# DotStix.net
KiCad netlist of a schematic drawn in EAGLE
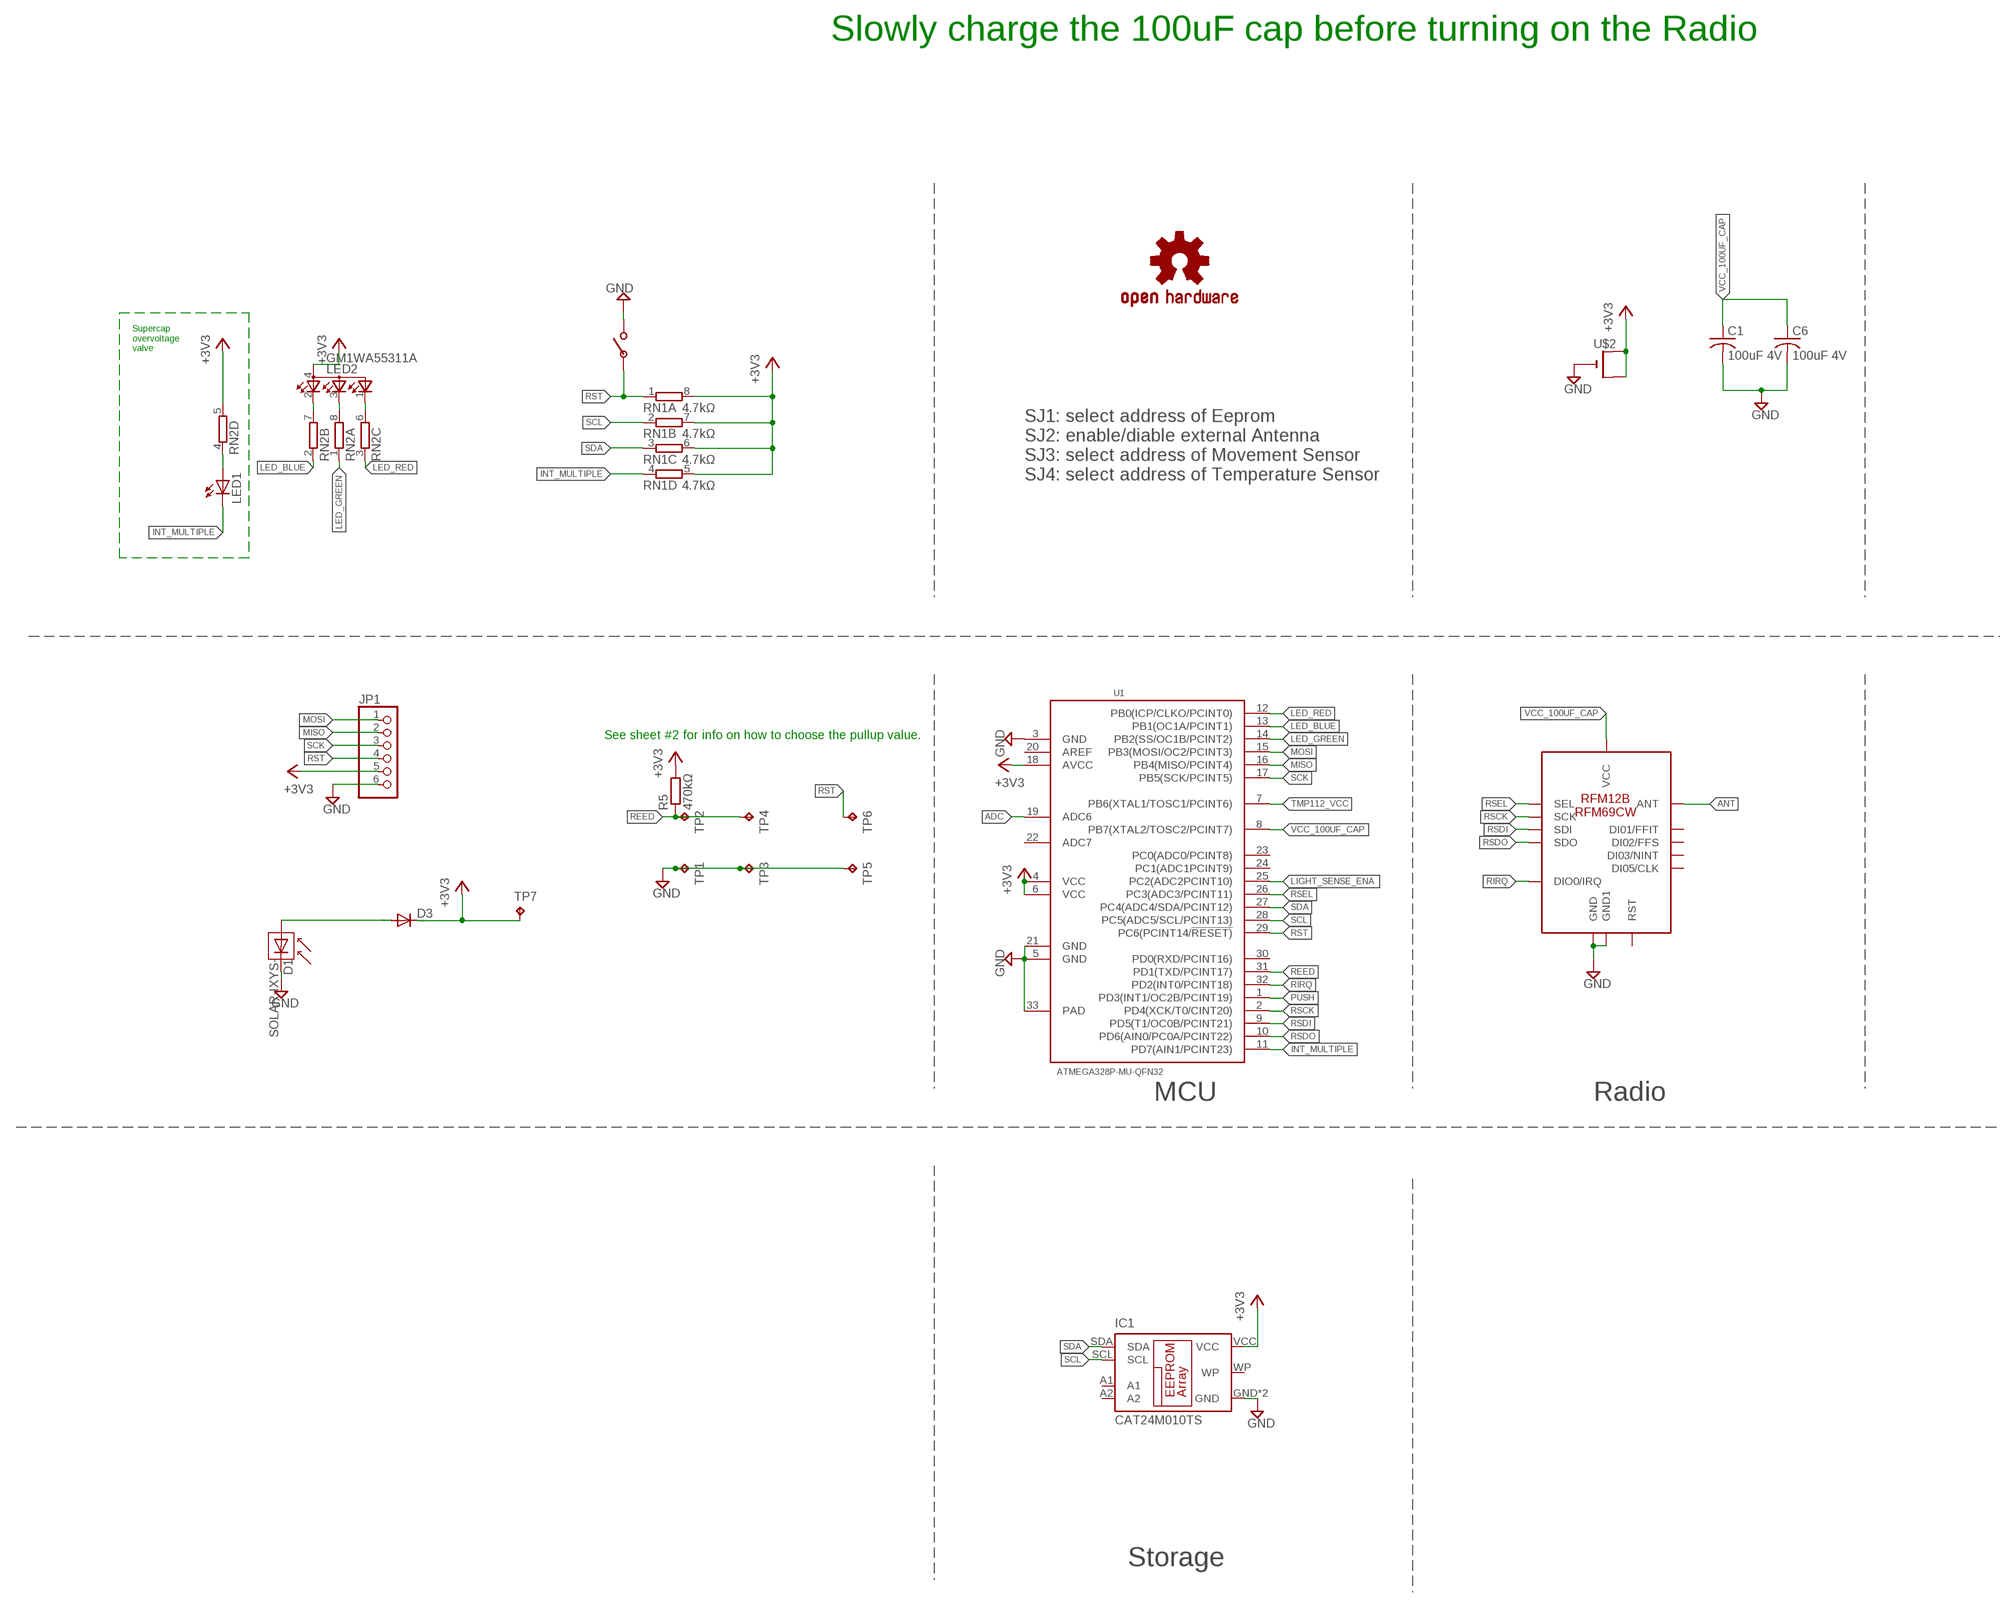
[diagram p0: schematic, sheet 1, part 1 of 2]
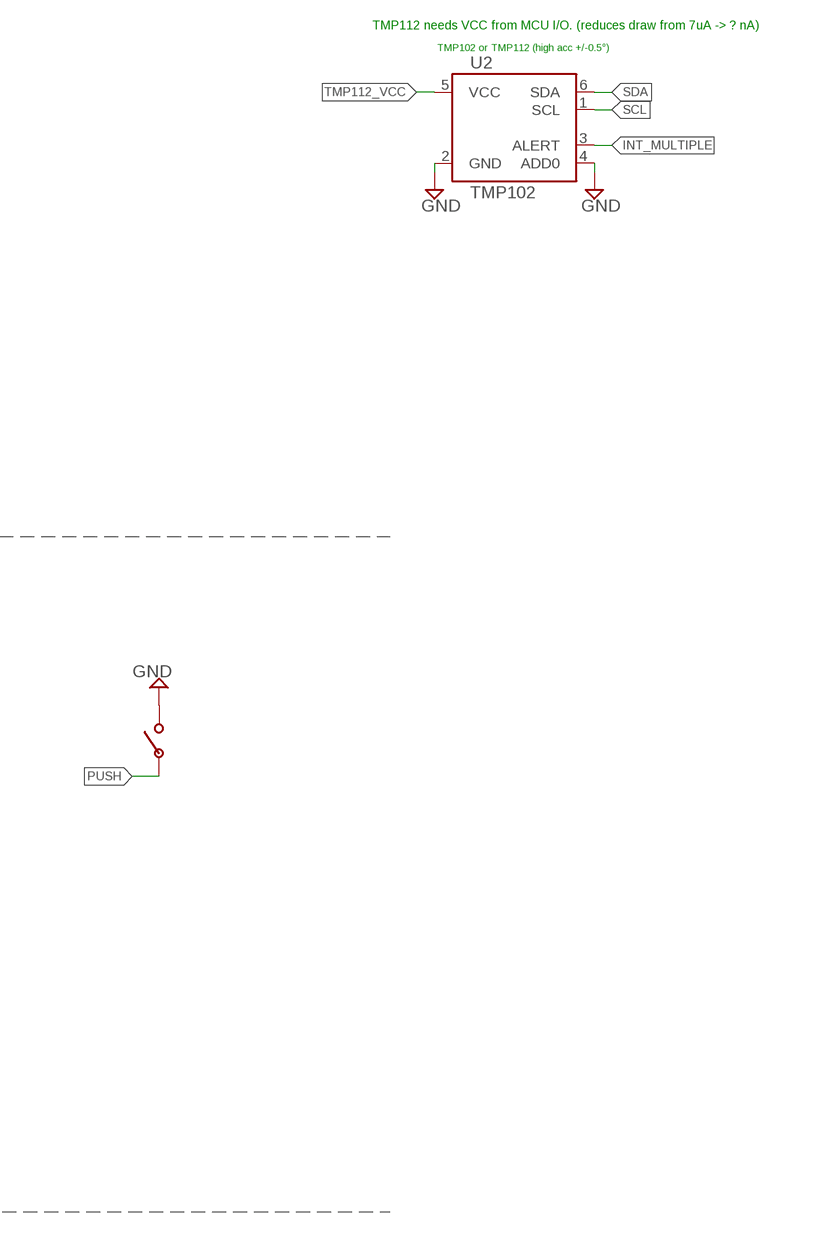
[diagram p1: schematic, sheet 1, part 2 of 2]
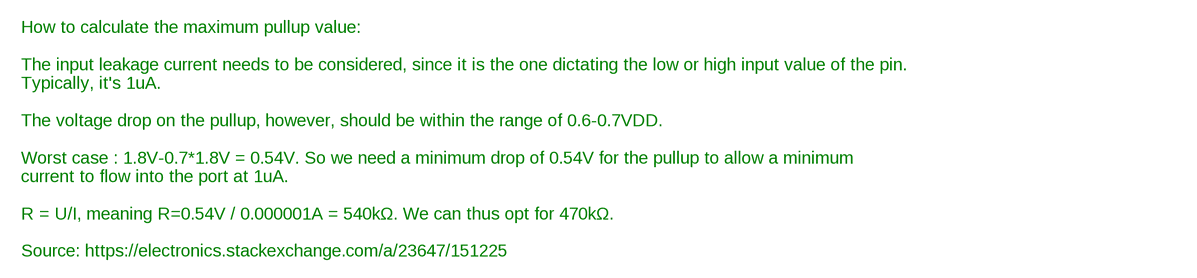
[diagram p2: schematic, sheet 2]

(export (version "E")
  (design (tool "Eeschema 10.0.6"))
  (components
    (comp (ref "C1")
      (value "100uF 4V")
      (footprint "eagle-import:C3216")
      (libsource (lib "eagle-import") (part "C-USC3216"))
    )
    (comp (ref "C6")
      (value "100uF 4V")
      (footprint "eagle-import:C3216")
      (libsource (lib "eagle-import") (part "C-USC3216"))
    )
    (comp (ref "D1")
      (value "SOLAR-IXYS-")
      (footprint "eagle-import:SOLARBIT-12X1")
      (libsource (lib "eagle-import") (part "SOLAR-IXYS-"))
    )
    (comp (ref "D3")
      (value "DIODE-SOD523")
      (footprint "eagle-import:SOD523")
      (libsource (lib "eagle-import") (part "DIODE-SOD523"))
    )
    (comp (ref "IC1")
      (value "CAT24M010TS")
      (footprint "eagle-import:TSSOP8")
      (fields (field (name "MF") "On Semiconductor") (field (name "MPN") "24C00T-E/ST"))
      (libsource (lib "eagle-import") (part "CAT24M01TS0"))
    )
    (comp (ref "JP1")
      (value "PINHD-1X6")
      (footprint "eagle-import:1X06")
      (libsource (lib "eagle-import") (part "PINHD-1X6"))
    )
    (comp (ref "LED1")
      (value "LEDCHIP-LED0603")
      (footprint "eagle-import:CHIP-LED0603")
      (libsource (lib "eagle-import") (part "LEDCHIP-LED0603"))
    )
    (comp (ref "LED2")
      (value "GM1WA55311A")
      (footprint "eagle-import:GM1WA55311A")
      (libsource (lib "eagle-import") (part "GM1WA55311A"))
    )
    (comp (ref "LOGO1")
      (value "OSHW-LOGOS")
      (footprint "eagle-import:OSHW-LOGO-S")
      (libsource (lib "eagle-import") (part "OSHW-LOGOS"))
    )
    (comp (ref "R5")
      (value "470kΩ")
      (footprint "eagle-import:R0603")
      (libsource (lib "eagle-import") (part "R-EU_R0603"))
    )
    (comp (ref "RN1")
      (value "4.7kΩ")
      (footprint "eagle-import:4X0402ARV341")
      (libsource (lib "eagle-import") (part "4R-N0402ARV341"))
    )
    (comp (ref "RN2")
      (value "4R-N0402ARV341")
      (footprint "eagle-import:4X0402ARV341")
      (libsource (lib "eagle-import") (part "4R-N0402ARV341"))
    )
    (comp (ref "TP1")
      (value "TPTP20SQ")
      (footprint "eagle-import:TP20SQ")
      (libsource (lib "eagle-import") (part "TPTP20SQ"))
    )
    (comp (ref "TP2")
      (value "TPTP20SQ")
      (footprint "eagle-import:TP20SQ")
      (libsource (lib "eagle-import") (part "TPTP20SQ"))
    )
    (comp (ref "TP3")
      (value "TPTP20SQ")
      (footprint "eagle-import:TP20SQ")
      (libsource (lib "eagle-import") (part "TPTP20SQ"))
    )
    (comp (ref "TP4")
      (value "TPTP20SQ")
      (footprint "eagle-import:TP20SQ")
      (libsource (lib "eagle-import") (part "TPTP20SQ"))
    )
    (comp (ref "TP5")
      (value "TPTP20SQ")
      (footprint "eagle-import:TP20SQ")
      (libsource (lib "eagle-import") (part "TPTP20SQ"))
    )
    (comp (ref "TP6")
      (value "TPTP20SQ")
      (footprint "eagle-import:TP20SQ")
      (libsource (lib "eagle-import") (part "TPTP20SQ"))
    )
    (comp (ref "TP7")
      (value "TPTP20SQ")
      (footprint "eagle-import:TP20SQ")
      (libsource (lib "eagle-import") (part "testpad_385_TPTP20SQ"))
    )
    (comp (ref "U$1")
      (value "RFM12B/69CW")
      (footprint "eagle-import:RFM12B_69CW")
      (libsource (lib "eagle-import") (part "RFM12B/69CW"))
    )
    (comp (ref "U$2")
      (value "CR1220SMT")
      (footprint "eagle-import:CR1220-SMD")
      (libsource (lib "eagle-import") (part "CR1220SMT"))
    )
    (comp (ref "U$3")
      (value "PUSHBUTTON_4X2.5")
      (footprint "eagle-import:PUSHBUTTON_4X2.5")
      (libsource (lib "eagle-import") (part "PUSHBUTTON_4X2.5"))
    )
    (comp (ref "U$4")
      (value "PUSHBUTTON_4X2.5")
      (footprint "eagle-import:PUSHBUTTON_4X2.5")
      (libsource (lib "eagle-import") (part "PUSHBUTTON_4X2.5"))
    )
    (comp (ref "U1")
      (value "ATMEGA328P-MU-QFN32")
      (footprint "eagle-import:QFN32G-0.5-5X5MM")
      (fields (field (name "MPN") "ATMEGA328P-MU"))
      (libsource (lib "eagle-import") (part "MCU-ATMEGA328P-MU(QFN32)"))
    )
    (comp (ref "U2")
      (value "TMP102")
      (footprint "eagle-import:SOT563")
      (libsource (lib "eagle-import") (part "TMP102"))
    )
  )
  (nets
    (net (code "1") (name "+3V3") (class "Default")
      (node (ref "D3") (pin "C") (pinfunction "C_C") (pintype "passive"))
      (node (ref "IC1") (pin "VCC") (pinfunction "VCC_VCC") (pintype "power_in"))
      (node (ref "JP1") (pin "5") (pinfunction "5_5") (pintype "passive"))
      (node (ref "LED2") (pin "4") (pinfunction "A_4") (pintype "passive"))
      (node (ref "R5") (pin "2") (pinfunction "2_2") (pintype "passive"))
      (node (ref "RN1") (pin "5") (pinfunction "2_5") (pintype "passive"))
      (node (ref "RN1") (pin "6") (pinfunction "2_6") (pintype "passive"))
      (node (ref "RN1") (pin "7") (pinfunction "2_7") (pintype "passive"))
      (node (ref "RN1") (pin "8") (pinfunction "2_8") (pintype "passive"))
      (node (ref "RN2") (pin "5") (pinfunction "2_5") (pintype "passive"))
      (node (ref "TP7") (pin "TP") (pinfunction "TP_TP") (pintype "input"))
      (node (ref "U$2") (pin "+$1") (pinfunction "+_+$1") (pintype "passive"))
      (node (ref "U$2") (pin "+$2") (pinfunction "+1_+$2") (pintype "passive"))
      (node (ref "U1") (pin "18") (pinfunction "AVCC_18") (pintype "bidirectional"))
      (node (ref "U1") (pin "4") (pinfunction "VCC_4") (pintype "bidirectional"))
      (node (ref "U1") (pin "6") (pinfunction "VCC_6") (pintype "bidirectional"))
    )
    (net (code "2") (name "ADC") (class "Default")
      (node (ref "U1") (pin "19") (pinfunction "ADC6_19") (pintype "bidirectional"))
    )
    (net (code "3") (name "ANT") (class "Default")
      (node (ref "U$1") (pin "ANT") (pinfunction "ANT_ANT") (pintype "passive"))
    )
    (net (code "4") (name "GND") (class "Default")
      (node (ref "C1") (pin "2") (pinfunction "2_2") (pintype "passive"))
      (node (ref "C6") (pin "2") (pinfunction "2_2") (pintype "passive"))
      (node (ref "D1") (pin "-") (pinfunction "C_-") (pintype "passive"))
      (node (ref "IC1") (pin "GND") (pinfunction "GND_GND") (pintype "power_in"))
      (node (ref "IC1") (pin "NC") (pinfunction "GND_NC") (pintype "power_in"))
      (node (ref "JP1") (pin "6") (pinfunction "6_6") (pintype "passive"))
      (node (ref "TP1") (pin "TP") (pinfunction "TP_TP") (pintype "input"))
      (node (ref "TP3") (pin "TP") (pinfunction "TP_TP") (pintype "input"))
      (node (ref "TP5") (pin "TP") (pinfunction "TP_TP") (pintype "input"))
      (node (ref "U$1") (pin "GND") (pinfunction "GND_GND") (pintype "power_in"))
      (node (ref "U$1") (pin "GND1") (pinfunction "GND1_GND1") (pintype "power_in"))
      (node (ref "U$2") (pin "-") (pinfunction "-_-") (pintype "passive"))
      (node (ref "U$3") (pin "P$2") (pinfunction "P$2_P$2") (pintype "bidirectional"))
      (node (ref "U$4") (pin "P$2") (pinfunction "P$2_P$2") (pintype "bidirectional"))
      (node (ref "U1") (pin "21") (pinfunction "GND_21") (pintype "bidirectional"))
      (node (ref "U1") (pin "3") (pinfunction "GND_3") (pintype "bidirectional"))
      (node (ref "U1") (pin "33") (pinfunction "PAD_33") (pintype "bidirectional"))
      (node (ref "U1") (pin "5") (pinfunction "GND_5") (pintype "bidirectional"))
      (node (ref "U2") (pin "2") (pinfunction "GND_2") (pintype "bidirectional"))
      (node (ref "U2") (pin "4") (pinfunction "ADD0_4") (pintype "bidirectional"))
    )
    (net (code "5") (name "INT_MULTIPLE") (class "Default")
      (node (ref "LED1") (pin "C") (pinfunction "C_C") (pintype "passive"))
      (node (ref "RN1") (pin "4") (pinfunction "1_4") (pintype "passive"))
      (node (ref "U1") (pin "11") (pinfunction "PD7(AIN1/PCINT23)_11") (pintype "bidirectional"))
      (node (ref "U2") (pin "3") (pinfunction "ALERT_3") (pintype "bidirectional"))
    )
    (net (code "6") (name "LED_BLUE") (class "Default")
      (node (ref "RN2") (pin "2") (pinfunction "1_2") (pintype "passive"))
      (node (ref "U1") (pin "13") (pinfunction "PB1(OC1A/PCINT1)_13") (pintype "bidirectional"))
    )
    (net (code "7") (name "LED_GREEN") (class "Default")
      (node (ref "RN2") (pin "1") (pinfunction "1_1") (pintype "passive"))
      (node (ref "U1") (pin "14") (pinfunction "PB2(SS/OC1B/PCINT2)_14") (pintype "bidirectional"))
    )
    (net (code "8") (name "LED_RED") (class "Default")
      (node (ref "RN2") (pin "3") (pinfunction "1_3") (pintype "passive"))
      (node (ref "U1") (pin "12") (pinfunction "PB0(ICP/CLKO/PCINT0)_12") (pintype "bidirectional"))
    )
    (net (code "9") (name "LIGHT_SENSE_ENA") (class "Default")
      (node (ref "U1") (pin "25") (pinfunction "PC2(ADC2PCINT10)_25") (pintype "bidirectional"))
    )
    (net (code "10") (name "MISO") (class "Default")
      (node (ref "JP1") (pin "2") (pinfunction "2_2") (pintype "passive"))
      (node (ref "U1") (pin "16") (pinfunction "PB4(MISO/PCINT4)_16") (pintype "bidirectional"))
    )
    (net (code "11") (name "MOSI") (class "Default")
      (node (ref "JP1") (pin "1") (pinfunction "1_1") (pintype "passive"))
      (node (ref "U1") (pin "15") (pinfunction "PB3(MOSI/OC2/PCINT3)_15") (pintype "bidirectional"))
    )
    (net (code "12") (name "Net-(D1-A)") (class "Default")
      (node (ref "D1") (pin "+") (pinfunction "A_+") (pintype "passive"))
      (node (ref "D3") (pin "A") (pinfunction "A_A") (pintype "passive"))
    )
    (net (code "13") (name "Net-(LED2-CBLUE)") (class "Default")
      (node (ref "LED2") (pin "3") (pinfunction "CBLUE_3") (pintype "passive"))
      (node (ref "RN2") (pin "8") (pinfunction "2_8") (pintype "passive"))
    )
    (net (code "14") (name "Net-(LED2-CGREEN)") (class "Default")
      (node (ref "LED2") (pin "1") (pinfunction "CGREEN_1") (pintype "passive"))
      (node (ref "RN2") (pin "6") (pinfunction "2_6") (pintype "passive"))
    )
    (net (code "15") (name "Net-(LED2-CRED)") (class "Default")
      (node (ref "LED2") (pin "2") (pinfunction "CRED_2") (pintype "passive"))
      (node (ref "RN2") (pin "7") (pinfunction "2_7") (pintype "passive"))
    )
    (net (code "16") (name "Net-(RN2D-1)") (class "Default")
      (node (ref "LED1") (pin "A") (pinfunction "A_A") (pintype "passive"))
      (node (ref "RN2") (pin "4") (pinfunction "1_4") (pintype "passive"))
    )
    (net (code "17") (name "PUSH") (class "Default")
      (node (ref "U$4") (pin "P$1") (pinfunction "P$1_P$1") (pintype "bidirectional"))
      (node (ref "U1") (pin "1") (pinfunction "PD3(INT1/OC2B/PCINT19)_1") (pintype "bidirectional"))
    )
    (net (code "18") (name "REED") (class "Default")
      (node (ref "R5") (pin "1") (pinfunction "1_1") (pintype "passive"))
      (node (ref "TP2") (pin "TP") (pinfunction "TP_TP") (pintype "input"))
      (node (ref "TP4") (pin "TP") (pinfunction "TP_TP") (pintype "input"))
      (node (ref "U1") (pin "31") (pinfunction "PD1(TXD/PCINT17)_31") (pintype "bidirectional"))
    )
    (net (code "19") (name "RIRQ") (class "Default")
      (node (ref "U$1") (pin "IRQ") (pinfunction "DIO0/IRQ_IRQ") (pintype "open_collector"))
      (node (ref "U1") (pin "32") (pinfunction "PD2(INT0/PCINT18)_32") (pintype "bidirectional"))
    )
    (net (code "20") (name "RSCK") (class "Default")
      (node (ref "U$1") (pin "SCK") (pinfunction "SCK_SCK") (pintype "input"))
      (node (ref "U1") (pin "2") (pinfunction "PD4(XCK/T0/CINT20)_2") (pintype "bidirectional"))
    )
    (net (code "21") (name "RSDI") (class "Default")
      (node (ref "U$1") (pin "SDI") (pinfunction "SDI_SDI") (pintype "input"))
      (node (ref "U1") (pin "9") (pinfunction "PD5(T1/OC0B/PCINT21)_9") (pintype "bidirectional"))
    )
    (net (code "22") (name "RSDO") (class "Default")
      (node (ref "U$1") (pin "SDO") (pinfunction "SDO_SDO") (pintype "output"))
      (node (ref "U1") (pin "10") (pinfunction "PD6(AIN0/PC0A/PCINT22)_10") (pintype "bidirectional"))
    )
    (net (code "23") (name "RSEL") (class "Default")
      (node (ref "U$1") (pin "SEL") (pinfunction "SEL_SEL") (pintype "input"))
      (node (ref "U1") (pin "26") (pinfunction "PC3(ADC3/PCINT11)_26") (pintype "bidirectional"))
    )
    (net (code "24") (name "RST") (class "Default")
      (node (ref "JP1") (pin "4") (pinfunction "4_4") (pintype "passive"))
      (node (ref "RN1") (pin "1") (pinfunction "1_1") (pintype "passive"))
      (node (ref "TP6") (pin "TP") (pinfunction "TP_TP") (pintype "input"))
      (node (ref "U$3") (pin "P$1") (pinfunction "P$1_P$1") (pintype "bidirectional"))
      (node (ref "U1") (pin "29") (pinfunction "PC6(PCINT14/~{RESET})_29") (pintype "bidirectional"))
    )
    (net (code "25") (name "SCK") (class "Default")
      (node (ref "JP1") (pin "3") (pinfunction "3_3") (pintype "passive"))
      (node (ref "U1") (pin "17") (pinfunction "PB5(SCK/PCINT5)_17") (pintype "bidirectional"))
    )
    (net (code "26") (name "SCL") (class "Default")
      (node (ref "IC1") (pin "SCL") (pinfunction "SCL_SCL") (pintype "input"))
      (node (ref "RN1") (pin "2") (pinfunction "1_2") (pintype "passive"))
      (node (ref "U1") (pin "28") (pinfunction "PC5(ADC5/SCL/PCINT13)_28") (pintype "bidirectional"))
      (node (ref "U2") (pin "1") (pinfunction "SCL_1") (pintype "bidirectional"))
    )
    (net (code "27") (name "SDA") (class "Default")
      (node (ref "IC1") (pin "SDA") (pinfunction "SDA_SDA") (pintype "bidirectional"))
      (node (ref "RN1") (pin "3") (pinfunction "1_3") (pintype "passive"))
      (node (ref "U1") (pin "27") (pinfunction "PC4(ADC4/SDA/PCINT12)_27") (pintype "bidirectional"))
      (node (ref "U2") (pin "6") (pinfunction "SDA_6") (pintype "bidirectional"))
    )
    (net (code "28") (name "TMP112_VCC") (class "Default")
      (node (ref "U1") (pin "7") (pinfunction "PB6(XTAL1/TOSC1/PCINT6)_7") (pintype "bidirectional"))
      (node (ref "U2") (pin "5") (pinfunction "VCC_5") (pintype "bidirectional"))
    )
    (net (code "29") (name "VCC_100UF_CAP") (class "Default")
      (node (ref "C1") (pin "1") (pinfunction "1_1") (pintype "passive"))
      (node (ref "C6") (pin "1") (pinfunction "1_1") (pintype "passive"))
      (node (ref "U$1") (pin "VDD") (pinfunction "VCC_VDD") (pintype "power_in"))
      (node (ref "U1") (pin "8") (pinfunction "PB7(XTAL2/TOSC2/PCINT7)_8") (pintype "bidirectional"))
    )
    (net (code "30") (name "unconnected-(IC1-PadA1)") (class "Default")
      (node (ref "IC1") (pin "A1") (pinfunction "A1_A1") (pintype "bidirectional"))
    )
    (net (code "31") (name "unconnected-(IC1-PadA2)") (class "Default")
      (node (ref "IC1") (pin "A2") (pinfunction "A2_A2") (pintype "bidirectional"))
    )
    (net (code "32") (name "unconnected-(IC1-PadWP)") (class "Default")
      (node (ref "IC1") (pin "WP") (pinfunction "WP_WP") (pintype "bidirectional"))
    )
    (net (code "33") (name "unconnected-(U$1-DI01{slash}FFIT-PadFFIT)") (class "Default")
      (node (ref "U$1") (pin "FFIT") (pinfunction "DI01/FFIT_FFIT") (pintype "passive"))
    )
    (net (code "34") (name "unconnected-(U$1-DI02{slash}FFS-PadFFS)") (class "Default")
      (node (ref "U$1") (pin "FFS") (pinfunction "DI02/FFS_FFS") (pintype "bidirectional"))
    )
    (net (code "35") (name "unconnected-(U$1-DI03{slash}NINT-PadNINT)") (class "Default")
      (node (ref "U$1") (pin "NINT") (pinfunction "DI03/NINT_NINT") (pintype "passive"))
    )
    (net (code "36") (name "unconnected-(U$1-DI05{slash}CLK-PadCLK)") (class "Default")
      (node (ref "U$1") (pin "CLK") (pinfunction "DI05/CLK_CLK") (pintype "passive"))
    )
    (net (code "37") (name "unconnected-(U$1-PadRST)") (class "Default")
      (node (ref "U$1") (pin "RST") (pinfunction "RST_RST") (pintype "open_collector"))
    )
    (net (code "38") (name "unconnected-(U1-ADC7-Pad22)") (class "Default")
      (node (ref "U1") (pin "22") (pinfunction "ADC7_22") (pintype "bidirectional"))
    )
    (net (code "39") (name "unconnected-(U1-AREF-Pad20)") (class "Default")
      (node (ref "U1") (pin "20") (pinfunction "AREF_20") (pintype "bidirectional"))
    )
    (net (code "40") (name "unconnected-(U1-PC0(ADC0{slash}PCINT8)-Pad23)") (class "Default")
      (node (ref "U1") (pin "23") (pinfunction "PC0(ADC0/PCINT8)_23") (pintype "bidirectional"))
    )
    (net (code "41") (name "unconnected-(U1-PC1(ADC1PCINT9)-Pad24)") (class "Default")
      (node (ref "U1") (pin "24") (pinfunction "PC1(ADC1PCINT9)_24") (pintype "bidirectional"))
    )
    (net (code "42") (name "unconnected-(U1-PD0(RXD{slash}PCINT16)-Pad30)") (class "Default")
      (node (ref "U1") (pin "30") (pinfunction "PD0(RXD/PCINT16)_30") (pintype "bidirectional"))
    )
  )
)
